# Page06_CPU_IO.net
KiCad netlist of a schematic drawn in Altium Designer
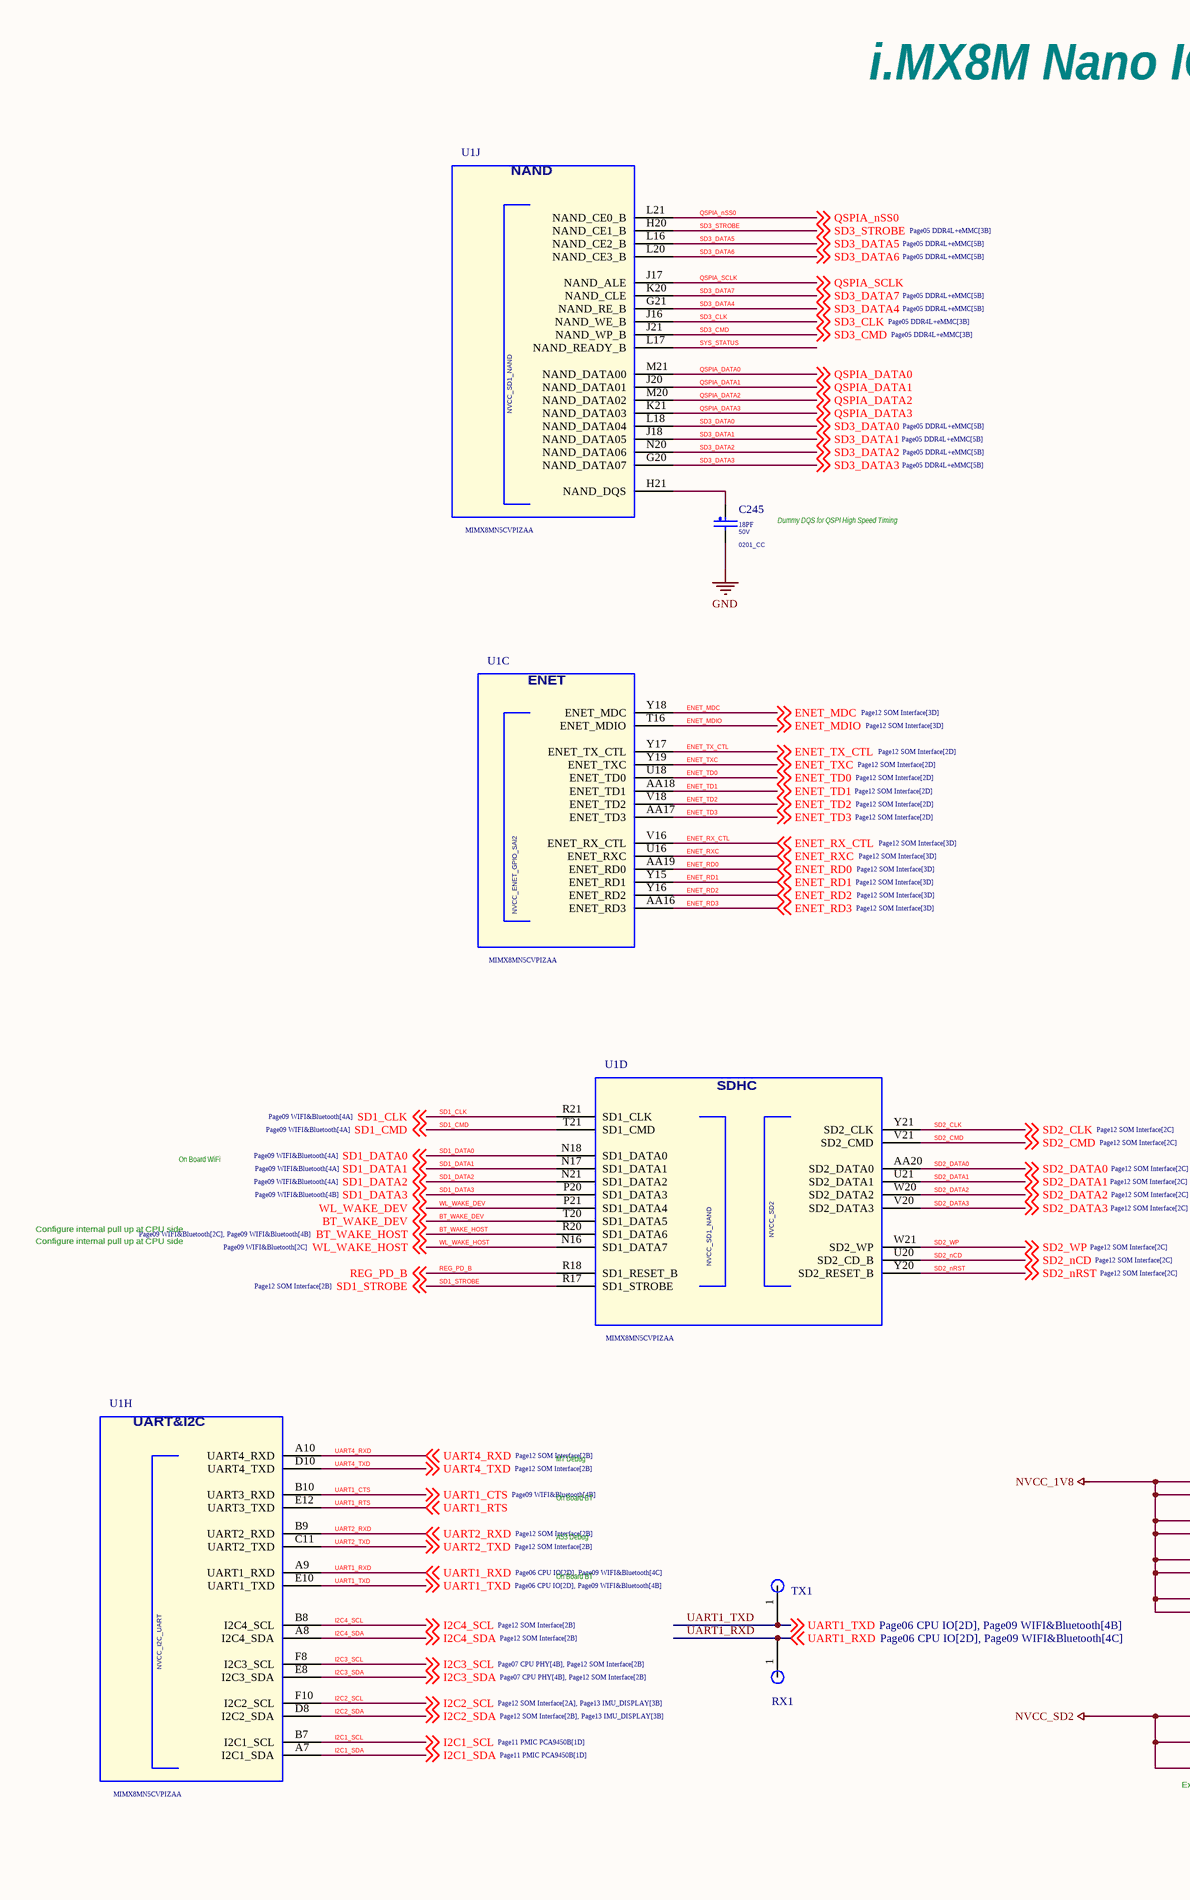
[diagram p0: Page06 CPU IO.SchDoc, left]
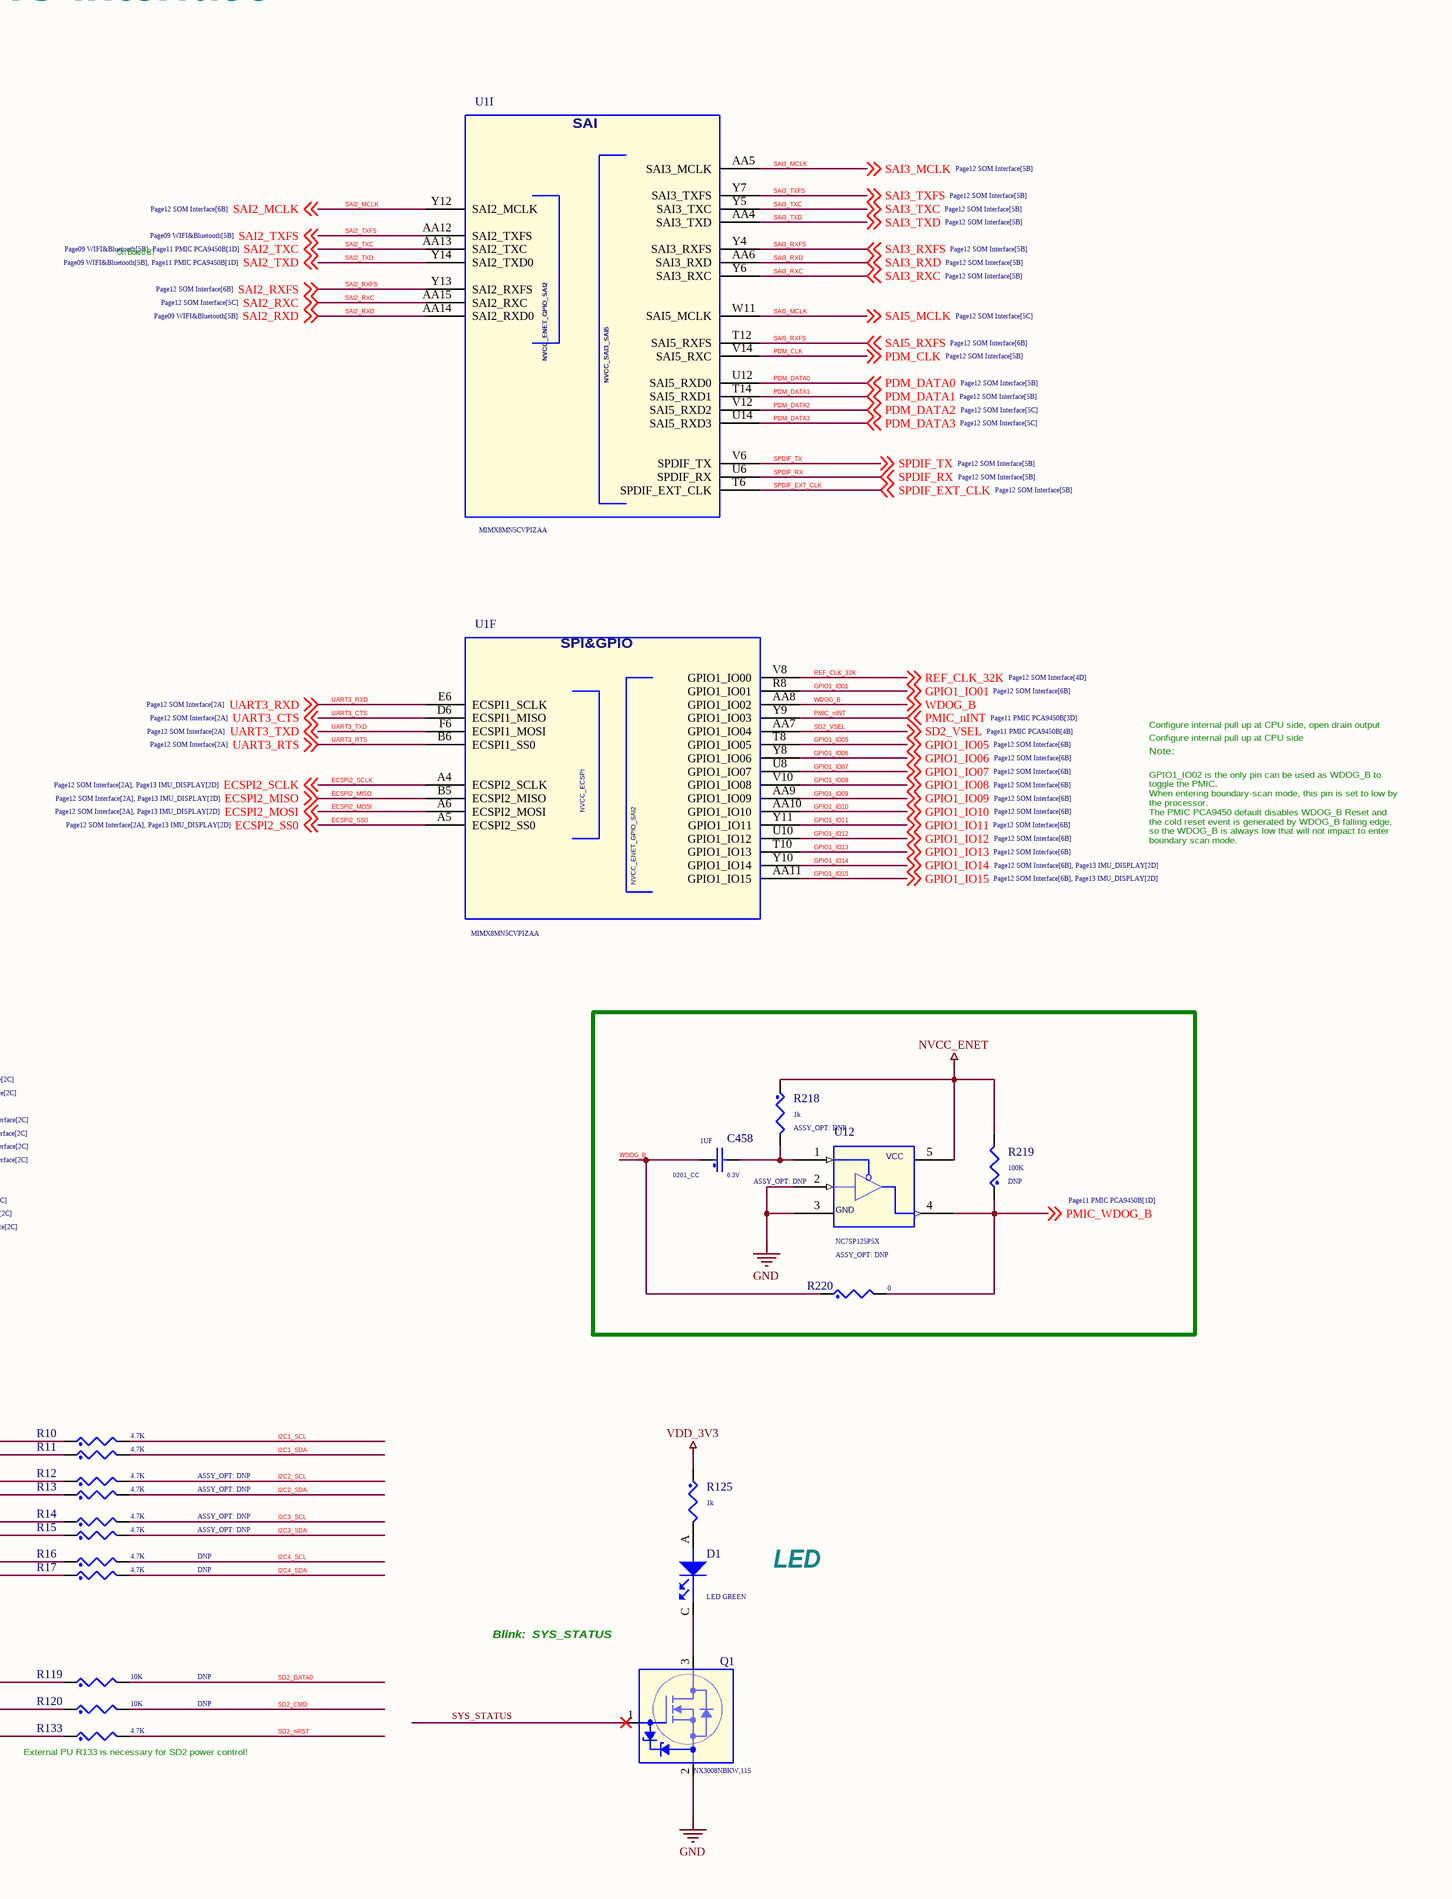
[diagram p1: Page06 CPU IO.SchDoc, right]

(export (version "E")
  (design (tool "Eeschema 10.0.6"))
  (components
    (comp (ref "C245")
      (value "18PF")
      (footprint "0201_CC - C")
      (description "CAP CER 18pF 50V 5% C0G 0201")
      (fields
        (field (name "VOLTAGE") "50V")
        (field (name "TOLERANCE") "5%")
        (field (name "PCB FOOTPRINT") "0201_CC")
      )
      (libsource (lib "*") (part "CAP_NP"))
    )
    (comp (ref "C458")
      (value "1UF")
      (footprint "0201_CC - C")
      (description "CAP CER 1uF 6.3V 20% X5R 0201")
      (fields
        (field (name "ASSY_OPT") "DNP")
        (field (name "PCB FOOTPRINT") "0201_CC")
        (field (name "TOLERANCE") "20%")
        (field (name "VOLTAGE") "6.3V")
      )
      (libsource (lib "*") (part "CAP_NP"))
    )
    (comp (ref "D1")
      (value "LED GREEN")
      (footprint "LED_0603")
      (description "LED GRN SGL 25MA SMT 0603")
      (fields (field (name "VOLTAGE") "2V"))
      (libsource (lib "*") (part "LED"))
    )
    (comp (ref "Q1")
      (value "NX3008NBKW,115")
      (footprint "SOT65P210X110-3N")
      (description "TRAN NMOS SW 30V 350mA AEC-Q101 SC-70")
      (libsource (lib "*") (part "NMOS_NX3008NBK"))
    )
    (comp (ref "R10")
      (value "4.7K")
      (footprint "0201_RES")
      (description "RES MF 4.7K 1/20W 5% AEC-Q200 0201")
      (fields (field (name "TOLERANCE") "5%"))
      (libsource (lib "*") (part "RES"))
    )
    (comp (ref "R11")
      (value "4.7K")
      (footprint "0201_RES")
      (description "RES MF 4.7K 1/20W 5% AEC-Q200 0201")
      (fields (field (name "TOLERANCE") "5%"))
      (libsource (lib "*") (part "RES"))
    )
    (comp (ref "R12")
      (value "4.7K")
      (footprint "0201_RES")
      (description "RES MF 4.7K 1/20W 5% AEC-Q200 0201")
      (fields (field (name "ASSY_OPT") "DNP") (field (name "TOLERANCE") "5%"))
      (libsource (lib "*") (part "RES"))
    )
    (comp (ref "R13")
      (value "4.7K")
      (footprint "0201_RES")
      (description "RES MF 4.7K 1/20W 5% AEC-Q200 0201")
      (fields (field (name "ASSY_OPT") "DNP") (field (name "TOLERANCE") "5%"))
      (libsource (lib "*") (part "RES"))
    )
    (comp (ref "R14")
      (value "4.7K")
      (footprint "0201_RES")
      (description "RES MF 4.7K 1/20W 5% AEC-Q200 0201")
      (fields (field (name "ASSY_OPT") "DNP") (field (name "TOLERANCE") "5%"))
      (libsource (lib "*") (part "RES"))
    )
    (comp (ref "R15")
      (value "4.7K")
      (footprint "0201_RES")
      (description "RES MF 4.7K 1/20W 5% AEC-Q200 0201")
      (fields (field (name "ASSY_OPT") "DNP") (field (name "TOLERANCE") "5%"))
      (libsource (lib "*") (part "RES"))
    )
    (comp (ref "R16")
      (value "4.7K")
      (footprint "0201_RES")
      (description "RES MF 4.7K 1/20W 5% AEC-Q200 0201")
      (fields (field (name "ASSY_OPT") "DNP") (field (name "TOLERANCE") "5%"))
      (libsource (lib "*") (part "RES"))
    )
    (comp (ref "R17")
      (value "4.7K")
      (footprint "0201_RES")
      (description "RES MF 4.7K 1/20W 5% AEC-Q200 0201")
      (fields (field (name "ASSY_OPT") "DNP") (field (name "TOLERANCE") "5%"))
      (libsource (lib "*") (part "RES"))
    )
    (comp (ref "R119")
      (value "10K")
      (footprint "0201_RES")
      (description "RES MF 10K 1/20W 5% 0201")
      (fields (field (name "ASSY_OPT") "DNP") (field (name "TOLERANCE") "5%"))
      (libsource (lib "*") (part "RES"))
    )
    (comp (ref "R120")
      (value "10K")
      (footprint "0201_RES")
      (description "RES MF 10K 1/20W 5% 0201")
      (fields (field (name "ASSY_OPT") "DNP") (field (name "TOLERANCE") "5%"))
      (libsource (lib "*") (part "RES"))
    )
    (comp (ref "R125")
      (value "1k")
      (footprint "0201_RES")
      (description "RES MF 1.0K OHM 1/20W 1% 30V -55+155C 0201")
      (fields (field (name "VOLTAGE") "30") (field (name "TOLERANCE") "1%"))
      (libsource (lib "*") (part "RES"))
    )
    (comp (ref "R133")
      (value "4.7K")
      (footprint "0201_RES")
      (description "RES MF 4.7K 1/20W 5% AEC-Q200 0201")
      (fields (field (name "TOLERANCE") "5%"))
      (libsource (lib "*") (part "RES"))
    )
    (comp (ref "R218")
      (value "1k")
      (footprint "0201_RES")
      (description "RES MF 1.0K OHM 1/20W 1% 30V -55+155C 0201")
      (fields (field (name "ASSY_OPT") "DNP") (field (name "TOLERANCE") "1%") (field (name "VOLTAGE") "30"))
      (libsource (lib "*") (part "RES"))
    )
    (comp (ref "R219")
      (value "100K")
      (footprint "0201_RES")
      (description "RES MF 100K 1/20W 1% 0201")
      (fields (field (name "ASSY_OPT") "DNP") (field (name "TOLERANCE") "1%"))
      (libsource (lib "*") (part "RES"))
    )
    (comp (ref "R220")
      (value "0")
      (footprint "0402_CC_RES")
      (description "RES MF ZERO OHM 1/16W 5% 0402")
      (fields (field (name "TOLERANCE") "5%") (field (name "VOLTAGE") "1/16W"))
      (libsource (lib "*") (part "RES"))
    )
    (comp (ref "RX1")
      (value "Test Pin1")
      (footprint "Test Pin")
      (libsource (lib "Altium starter project NANO") (part "Test Pin1"))
    )
    (comp (ref "TX1")
      (value "Test Pin1")
      (footprint "Test Pin")
      (libsource (lib "Altium starter project NANO") (part "Test Pin1"))
    )
    (comp (ref "U1")
      (value "MIMX8MN5CVPIZAA")
      (footprint "BGA306C50P21X21_1100X1100X101")
      (description "IC CPU QUAD CORTEX A53+M7 1.4GHZ -- BGA306")
      (libsource (lib "*") (part "MIMX8MN"))
    )
    (comp (ref "U12")
      (value "NC7SP125P5X")
      (footprint "FP-MAA05A-IPC_B")
      (description "IC BUF TS 0.9-3.6V")
      (fields (field (name "ASSY_OPT") "DNP"))
      (libsource (lib "*") (part "1G125"))
    )
  )
  (nets
    (net (code "1") (name "/SYS_STATUS") (class "Default")
      (node (ref "Q1") (pin "1") (pinfunction "GATE_1") (pintype "passive"))
      (node (ref "U1") (pin "L17") (pinfunction "NAND_READY_B_L17") (pintype "passive"))
    )
    (net (code "2") (name "BT_WAKE_DEV") (class "Default")
      (node (ref "U1") (pin "T20") (pinfunction "SD1_DATA5_T20") (pintype "passive"))
    )
    (net (code "3") (name "BT_WAKE_HOST") (class "Default")
      (node (ref "U1") (pin "R20") (pinfunction "SD1_DATA6_R20") (pintype "passive"))
    )
    (net (code "4") (name "ECSPI2_MISO") (class "Default")
      (node (ref "U1") (pin "B5") (pinfunction "ECSPI2_MISO_B5") (pintype "passive"))
    )
    (net (code "5") (name "ECSPI2_MOSI") (class "Default")
      (node (ref "U1") (pin "A6") (pinfunction "ECSPI2_MOSI_A6") (pintype "passive"))
    )
    (net (code "6") (name "ECSPI2_SCLK") (class "Default")
      (node (ref "U1") (pin "A4") (pinfunction "ECSPI2_SCLK_A4") (pintype "passive"))
    )
    (net (code "7") (name "ECSPI2_SS0") (class "Default")
      (node (ref "U1") (pin "A5") (pinfunction "ECSPI2_SS0_A5") (pintype "passive"))
    )
    (net (code "8") (name "ENET_MDC") (class "Default")
      (node (ref "U1") (pin "Y18") (pinfunction "ENET_MDC_Y18") (pintype "passive"))
    )
    (net (code "9") (name "ENET_MDIO") (class "Default")
      (node (ref "U1") (pin "T16") (pinfunction "ENET_MDIO_T16") (pintype "passive"))
    )
    (net (code "10") (name "ENET_RD0") (class "Default")
      (node (ref "U1") (pin "AA19") (pinfunction "ENET_RD0_AA19") (pintype "passive"))
    )
    (net (code "11") (name "ENET_RD1") (class "Default")
      (node (ref "U1") (pin "Y15") (pinfunction "ENET_RD1_Y15") (pintype "passive"))
    )
    (net (code "12") (name "ENET_RD2") (class "Default")
      (node (ref "U1") (pin "Y16") (pinfunction "ENET_RD2_Y16") (pintype "passive"))
    )
    (net (code "13") (name "ENET_RD3") (class "Default")
      (node (ref "U1") (pin "AA16") (pinfunction "ENET_RD3_AA16") (pintype "passive"))
    )
    (net (code "14") (name "ENET_RXC") (class "Default")
      (node (ref "U1") (pin "U16") (pinfunction "ENET_RXC_U16") (pintype "passive"))
    )
    (net (code "15") (name "ENET_RX_CTL") (class "Default")
      (node (ref "U1") (pin "V16") (pinfunction "ENET_RX_CTL_V16") (pintype "passive"))
    )
    (net (code "16") (name "ENET_TD0") (class "Default")
      (node (ref "U1") (pin "U18") (pinfunction "ENET_TD0_U18") (pintype "passive"))
    )
    (net (code "17") (name "ENET_TD1") (class "Default")
      (node (ref "U1") (pin "AA18") (pinfunction "ENET_TD1_AA18") (pintype "passive"))
    )
    (net (code "18") (name "ENET_TD2") (class "Default")
      (node (ref "U1") (pin "V18") (pinfunction "ENET_TD2_V18") (pintype "passive"))
    )
    (net (code "19") (name "ENET_TD3") (class "Default")
      (node (ref "U1") (pin "AA17") (pinfunction "ENET_TD3_AA17") (pintype "passive"))
    )
    (net (code "20") (name "ENET_TXC") (class "Default")
      (node (ref "U1") (pin "Y19") (pinfunction "ENET_TXC_Y19") (pintype "passive"))
    )
    (net (code "21") (name "ENET_TX_CTL") (class "Default")
      (node (ref "U1") (pin "Y17") (pinfunction "ENET_TX_CTL_Y17") (pintype "passive"))
    )
    (net (code "22") (name "GND") (class "Default")
      (node (ref "C245") (pin "2") (pinfunction "2_2") (pintype "passive"))
      (node (ref "Q1") (pin "2") (pinfunction "SOURCE_2") (pintype "passive"))
      (node (ref "U12") (pin "2") (pinfunction "A_2") (pintype "input"))
      (node (ref "U12") (pin "3") (pinfunction "GND_3") (pintype "power_in"))
    )
    (net (code "23") (name "GPIO1_IO01") (class "Default")
      (node (ref "U1") (pin "R8") (pinfunction "GPIO1_IO01_R8") (pintype "passive"))
    )
    (net (code "24") (name "GPIO1_IO05") (class "Default")
      (node (ref "U1") (pin "T8") (pinfunction "GPIO1_IO05_T8") (pintype "passive"))
    )
    (net (code "25") (name "GPIO1_IO06") (class "Default")
      (node (ref "U1") (pin "Y8") (pinfunction "GPIO1_IO06_Y8") (pintype "passive"))
    )
    (net (code "26") (name "GPIO1_IO07") (class "Default")
      (node (ref "U1") (pin "U8") (pinfunction "GPIO1_IO07_U8") (pintype "passive"))
    )
    (net (code "27") (name "GPIO1_IO08") (class "Default")
      (node (ref "U1") (pin "V10") (pinfunction "GPIO1_IO08_V10") (pintype "passive"))
    )
    (net (code "28") (name "GPIO1_IO09") (class "Default")
      (node (ref "U1") (pin "AA9") (pinfunction "GPIO1_IO09_AA9") (pintype "passive"))
    )
    (net (code "29") (name "GPIO1_IO10") (class "Default")
      (node (ref "U1") (pin "AA10") (pinfunction "GPIO1_IO10_AA10") (pintype "passive"))
    )
    (net (code "30") (name "GPIO1_IO11") (class "Default")
      (node (ref "U1") (pin "Y11") (pinfunction "GPIO1_IO11_Y11") (pintype "passive"))
    )
    (net (code "31") (name "GPIO1_IO12") (class "Default")
      (node (ref "U1") (pin "U10") (pinfunction "GPIO1_IO12_U10") (pintype "passive"))
    )
    (net (code "32") (name "GPIO1_IO13") (class "Default")
      (node (ref "U1") (pin "T10") (pinfunction "GPIO1_IO13_T10") (pintype "passive"))
    )
    (net (code "33") (name "GPIO1_IO14") (class "Default")
      (node (ref "U1") (pin "Y10") (pinfunction "GPIO1_IO14_Y10") (pintype "passive"))
    )
    (net (code "34") (name "GPIO1_IO15") (class "Default")
      (node (ref "U1") (pin "AA11") (pinfunction "GPIO1_IO15_AA11") (pintype "passive"))
    )
    (net (code "35") (name "I2C1_SCL") (class "Default")
      (node (ref "R10") (pin "2") (pinfunction "2_2") (pintype "passive"))
      (node (ref "U1") (pin "B7") (pinfunction "I2C1_SCL_B7") (pintype "passive"))
    )
    (net (code "36") (name "I2C1_SDA") (class "Default")
      (node (ref "R11") (pin "2") (pinfunction "2_2") (pintype "passive"))
      (node (ref "U1") (pin "A7") (pinfunction "I2C1_SDA_A7") (pintype "passive"))
    )
    (net (code "37") (name "I2C2_SCL") (class "Default")
      (node (ref "R12") (pin "2") (pinfunction "2_2") (pintype "passive"))
      (node (ref "U1") (pin "F10") (pinfunction "I2C2_SCL_F10") (pintype "passive"))
    )
    (net (code "38") (name "I2C2_SDA") (class "Default")
      (node (ref "R13") (pin "2") (pinfunction "2_2") (pintype "passive"))
      (node (ref "U1") (pin "D8") (pinfunction "I2C2_SDA_D8") (pintype "passive"))
    )
    (net (code "39") (name "I2C3_SCL") (class "Default")
      (node (ref "R14") (pin "2") (pinfunction "2_2") (pintype "passive"))
      (node (ref "U1") (pin "F8") (pinfunction "I2C3_SCL_F8") (pintype "passive"))
    )
    (net (code "40") (name "I2C3_SDA") (class "Default")
      (node (ref "R15") (pin "2") (pinfunction "2_2") (pintype "passive"))
      (node (ref "U1") (pin "E8") (pinfunction "I2C3_SDA_E8") (pintype "passive"))
    )
    (net (code "41") (name "I2C4_SCL") (class "Default")
      (node (ref "R16") (pin "2") (pinfunction "2_2") (pintype "passive"))
      (node (ref "U1") (pin "B8") (pinfunction "I2C4_SCL_B8") (pintype "passive"))
    )
    (net (code "42") (name "I2C4_SDA") (class "Default")
      (node (ref "R17") (pin "2") (pinfunction "2_2") (pintype "passive"))
      (node (ref "U1") (pin "A8") (pinfunction "I2C4_SDA_A8") (pintype "passive"))
    )
    (net (code "43") (name "NVCC_1V8") (class "Default")
      (node (ref "R10") (pin "1") (pinfunction "1_1") (pintype "passive"))
      (node (ref "R11") (pin "1") (pinfunction "1_1") (pintype "passive"))
      (node (ref "R12") (pin "1") (pinfunction "1_1") (pintype "passive"))
      (node (ref "R13") (pin "1") (pinfunction "1_1") (pintype "passive"))
      (node (ref "R14") (pin "1") (pinfunction "1_1") (pintype "passive"))
      (node (ref "R15") (pin "1") (pinfunction "1_1") (pintype "passive"))
      (node (ref "R16") (pin "1") (pinfunction "1_1") (pintype "passive"))
      (node (ref "R17") (pin "1") (pinfunction "1_1") (pintype "passive"))
    )
    (net (code "44") (name "NVCC_ENET") (class "Default")
      (node (ref "R218") (pin "1") (pinfunction "1_1") (pintype "passive"))
      (node (ref "R219") (pin "2") (pinfunction "2_2") (pintype "passive"))
      (node (ref "U12") (pin "5") (pinfunction "VCC_5") (pintype "power_in"))
    )
    (net (code "45") (name "NVCC_SD2") (class "Default")
      (node (ref "R119") (pin "1") (pinfunction "1_1") (pintype "passive"))
      (node (ref "R120") (pin "1") (pinfunction "1_1") (pintype "passive"))
      (node (ref "R133") (pin "1") (pinfunction "1_1") (pintype "passive"))
    )
    (net (code "46") (name "Net-(D1-ANODE)") (class "Default")
      (node (ref "D1") (pin "A") (pinfunction "ANODE_A") (pintype "passive"))
      (node (ref "R125") (pin "2") (pinfunction "2_2") (pintype "passive"))
    )
    (net (code "47") (name "Net-(D1-CATHODE)") (class "Default")
      (node (ref "D1") (pin "C") (pinfunction "CATHODE_C") (pintype "passive"))
      (node (ref "Q1") (pin "3") (pinfunction "DRAIN_3") (pintype "passive"))
    )
    (net (code "48") (name "Net-(U1J-NAND_DQS)") (class "Default")
      (node (ref "C245") (pin "1") (pinfunction "1_1") (pintype "passive"))
      (node (ref "U1") (pin "H21") (pinfunction "NAND_DQS_H21") (pintype "passive"))
    )
    (net (code "49") (name "Net-(U12-~{OE})") (class "Default")
      (node (ref "C458") (pin "2") (pinfunction "2_2") (pintype "passive"))
      (node (ref "R218") (pin "2") (pinfunction "2_2") (pintype "passive"))
      (node (ref "U12") (pin "1") (pinfunction "~{OE}_1") (pintype "input"))
    )
    (net (code "50") (name "PDM_CLK") (class "Default")
      (node (ref "U1") (pin "V14") (pinfunction "SAI5_RXC_V14") (pintype "passive"))
    )
    (net (code "51") (name "PDM_DATA0") (class "Default")
      (node (ref "U1") (pin "U12") (pinfunction "SAI5_RXD0_U12") (pintype "passive"))
    )
    (net (code "52") (name "PDM_DATA1") (class "Default")
      (node (ref "U1") (pin "T14") (pinfunction "SAI5_RXD1_T14") (pintype "passive"))
    )
    (net (code "53") (name "PDM_DATA2") (class "Default")
      (node (ref "U1") (pin "V12") (pinfunction "SAI5_RXD2_V12") (pintype "passive"))
    )
    (net (code "54") (name "PDM_DATA3") (class "Default")
      (node (ref "U1") (pin "U14") (pinfunction "SAI5_RXD3_U14") (pintype "passive"))
    )
    (net (code "55") (name "PMIC_WDOG_B") (class "Default")
      (node (ref "R219") (pin "1") (pinfunction "1_1") (pintype "passive"))
      (node (ref "R220") (pin "2") (pinfunction "2_2") (pintype "passive"))
      (node (ref "U12") (pin "4") (pinfunction "Y_4") (pintype "output"))
    )
    (net (code "56") (name "PMIC_nINT") (class "Default")
      (node (ref "U1") (pin "Y9") (pinfunction "GPIO1_IO03_Y9") (pintype "passive"))
    )
    (net (code "57") (name "QSPIA_DATA0") (class "Default")
      (node (ref "U1") (pin "M21") (pinfunction "NAND_DATA00_M21") (pintype "passive"))
    )
    (net (code "58") (name "QSPIA_DATA1") (class "Default")
      (node (ref "U1") (pin "J20") (pinfunction "NAND_DATA01_J20") (pintype "passive"))
    )
    (net (code "59") (name "QSPIA_DATA2") (class "Default")
      (node (ref "U1") (pin "M20") (pinfunction "NAND_DATA02_M20") (pintype "passive"))
    )
    (net (code "60") (name "QSPIA_DATA3") (class "Default")
      (node (ref "U1") (pin "K21") (pinfunction "NAND_DATA03_K21") (pintype "passive"))
    )
    (net (code "61") (name "QSPIA_SCLK") (class "Default")
      (node (ref "U1") (pin "J17") (pinfunction "NAND_ALE_J17") (pintype "passive"))
    )
    (net (code "62") (name "QSPIA_nSS0") (class "Default")
      (node (ref "U1") (pin "L21") (pinfunction "NAND_CE0_B_L21") (pintype "passive"))
    )
    (net (code "63") (name "REF_CLK_32K") (class "Default")
      (node (ref "U1") (pin "V8") (pinfunction "GPIO1_IO00_V8") (pintype "passive"))
    )
    (net (code "64") (name "REG_PD_B") (class "Default")
      (node (ref "U1") (pin "R18") (pinfunction "SD1_RESET_B_R18") (pintype "passive"))
    )
    (net (code "65") (name "SAI2_MCLK") (class "Default")
      (node (ref "U1") (pin "Y12") (pinfunction "SAI2_MCLK_Y12") (pintype "passive"))
    )
    (net (code "66") (name "SAI2_RXC") (class "Default")
      (node (ref "U1") (pin "AA15") (pinfunction "SAI2_RXC_AA15") (pintype "passive"))
    )
    (net (code "67") (name "SAI2_RXD") (class "Default")
      (node (ref "U1") (pin "AA14") (pinfunction "SAI2_RXD0_AA14") (pintype "passive"))
    )
    (net (code "68") (name "SAI2_RXFS") (class "Default")
      (node (ref "U1") (pin "Y13") (pinfunction "SAI2_RXFS_Y13") (pintype "passive"))
    )
    (net (code "69") (name "SAI2_TXC") (class "Default")
      (node (ref "U1") (pin "AA13") (pinfunction "SAI2_TXC_AA13") (pintype "passive"))
    )
    (net (code "70") (name "SAI2_TXD") (class "Default")
      (node (ref "U1") (pin "Y14") (pinfunction "SAI2_TXD0_Y14") (pintype "passive"))
    )
    (net (code "71") (name "SAI2_TXFS") (class "Default")
      (node (ref "U1") (pin "AA12") (pinfunction "SAI2_TXFS_AA12") (pintype "passive"))
    )
    (net (code "72") (name "SAI3_MCLK") (class "Default")
      (node (ref "U1") (pin "AA5") (pinfunction "SAI3_MCLK_AA5") (pintype "passive"))
    )
    (net (code "73") (name "SAI3_RXC") (class "Default")
      (node (ref "U1") (pin "Y6") (pinfunction "SAI3_RXC_Y6") (pintype "passive"))
    )
    (net (code "74") (name "SAI3_RXD") (class "Default")
      (node (ref "U1") (pin "AA6") (pinfunction "SAI3_RXD_AA6") (pintype "passive"))
    )
    (net (code "75") (name "SAI3_RXFS") (class "Default")
      (node (ref "U1") (pin "Y4") (pinfunction "SAI3_RXFS_Y4") (pintype "passive"))
    )
    (net (code "76") (name "SAI3_TXC") (class "Default")
      (node (ref "U1") (pin "Y5") (pinfunction "SAI3_TXC_Y5") (pintype "passive"))
    )
    (net (code "77") (name "SAI3_TXD") (class "Default")
      (node (ref "U1") (pin "AA4") (pinfunction "SAI3_TXD_AA4") (pintype "passive"))
    )
    (net (code "78") (name "SAI3_TXFS") (class "Default")
      (node (ref "U1") (pin "Y7") (pinfunction "SAI3_TXFS_Y7") (pintype "passive"))
    )
    (net (code "79") (name "SAI5_MCLK") (class "Default")
      (node (ref "U1") (pin "W11") (pinfunction "SAI5_MCLK_W11") (pintype "passive"))
    )
    (net (code "80") (name "SAI5_RXFS") (class "Default")
      (node (ref "U1") (pin "T12") (pinfunction "SAI5_RXFS_T12") (pintype "passive"))
    )
    (net (code "81") (name "SD1_CLK") (class "Default")
      (node (ref "U1") (pin "R21") (pinfunction "SD1_CLK_R21") (pintype "passive"))
    )
    (net (code "82") (name "SD1_CMD") (class "Default")
      (node (ref "U1") (pin "T21") (pinfunction "SD1_CMD_T21") (pintype "passive"))
    )
    (net (code "83") (name "SD1_DATA0") (class "Default")
      (node (ref "U1") (pin "N18") (pinfunction "SD1_DATA0_N18") (pintype "passive"))
    )
    (net (code "84") (name "SD1_DATA1") (class "Default")
      (node (ref "U1") (pin "N17") (pinfunction "SD1_DATA1_N17") (pintype "passive"))
    )
    (net (code "85") (name "SD1_DATA2") (class "Default")
      (node (ref "U1") (pin "N21") (pinfunction "SD1_DATA2_N21") (pintype "passive"))
    )
    (net (code "86") (name "SD1_DATA3") (class "Default")
      (node (ref "U1") (pin "P20") (pinfunction "SD1_DATA3_P20") (pintype "passive"))
    )
    (net (code "87") (name "SD1_STROBE") (class "Default")
      (node (ref "U1") (pin "R17") (pinfunction "SD1_STROBE_R17") (pintype "passive"))
    )
    (net (code "88") (name "SD2_CLK") (class "Default")
      (node (ref "U1") (pin "Y21") (pinfunction "SD2_CLK_Y21") (pintype "passive"))
    )
    (net (code "89") (name "SD2_CMD") (class "Default")
      (node (ref "R120") (pin "2") (pinfunction "2_2") (pintype "passive"))
      (node (ref "U1") (pin "V21") (pinfunction "SD2_CMD_V21") (pintype "passive"))
    )
    (net (code "90") (name "SD2_DATA0") (class "Default")
      (node (ref "R119") (pin "2") (pinfunction "2_2") (pintype "passive"))
      (node (ref "U1") (pin "AA20") (pinfunction "SD2_DATA0_AA20") (pintype "passive"))
    )
    (net (code "91") (name "SD2_DATA1") (class "Default")
      (node (ref "U1") (pin "U21") (pinfunction "SD2_DATA1_U21") (pintype "passive"))
    )
    (net (code "92") (name "SD2_DATA2") (class "Default")
      (node (ref "U1") (pin "W20") (pinfunction "SD2_DATA2_W20") (pintype "passive"))
    )
    (net (code "93") (name "SD2_DATA3") (class "Default")
      (node (ref "U1") (pin "V20") (pinfunction "SD2_DATA3_V20") (pintype "passive"))
    )
    (net (code "94") (name "SD2_VSEL") (class "Default")
      (node (ref "U1") (pin "AA7") (pinfunction "GPIO1_IO04_AA7") (pintype "passive"))
    )
    (net (code "95") (name "SD2_WP") (class "Default")
      (node (ref "U1") (pin "W21") (pinfunction "SD2_WP_W21") (pintype "passive"))
    )
    (net (code "96") (name "SD2_nCD") (class "Default")
      (node (ref "U1") (pin "U20") (pinfunction "SD2_CD_B_U20") (pintype "passive"))
    )
    (net (code "97") (name "SD2_nRST") (class "Default")
      (node (ref "R133") (pin "2") (pinfunction "2_2") (pintype "passive"))
      (node (ref "U1") (pin "Y20") (pinfunction "SD2_RESET_B_Y20") (pintype "passive"))
    )
    (net (code "98") (name "SD3_CLK") (class "Default")
      (node (ref "U1") (pin "J16") (pinfunction "NAND_WE_B_J16") (pintype "passive"))
    )
    (net (code "99") (name "SD3_CMD") (class "Default")
      (node (ref "U1") (pin "J21") (pinfunction "NAND_WP_B_J21") (pintype "passive"))
    )
    (net (code "100") (name "SD3_DATA0") (class "Default")
      (node (ref "U1") (pin "L18") (pinfunction "NAND_DATA04_L18") (pintype "passive"))
    )
    (net (code "101") (name "SD3_DATA1") (class "Default")
      (node (ref "U1") (pin "J18") (pinfunction "NAND_DATA05_J18") (pintype "passive"))
    )
    (net (code "102") (name "SD3_DATA2") (class "Default")
      (node (ref "U1") (pin "N20") (pinfunction "NAND_DATA06_N20") (pintype "passive"))
    )
    (net (code "103") (name "SD3_DATA3") (class "Default")
      (node (ref "U1") (pin "G20") (pinfunction "NAND_DATA07_G20") (pintype "passive"))
    )
    (net (code "104") (name "SD3_DATA4") (class "Default")
      (node (ref "U1") (pin "G21") (pinfunction "NAND_RE_B_G21") (pintype "passive"))
    )
    (net (code "105") (name "SD3_DATA5") (class "Default")
      (node (ref "U1") (pin "L16") (pinfunction "NAND_CE2_B_L16") (pintype "passive"))
    )
    (net (code "106") (name "SD3_DATA6") (class "Default")
      (node (ref "U1") (pin "L20") (pinfunction "NAND_CE3_B_L20") (pintype "passive"))
    )
    (net (code "107") (name "SD3_DATA7") (class "Default")
      (node (ref "U1") (pin "K20") (pinfunction "NAND_CLE_K20") (pintype "passive"))
    )
    (net (code "108") (name "SD3_STROBE") (class "Default")
      (node (ref "U1") (pin "H20") (pinfunction "NAND_CE1_B_H20") (pintype "passive"))
    )
    (net (code "109") (name "SPDIF_EXT_CLK") (class "Default")
      (node (ref "U1") (pin "T6") (pinfunction "SPDIF_EXT_CLK_T6") (pintype "passive"))
    )
    (net (code "110") (name "SPDIF_RX") (class "Default")
      (node (ref "U1") (pin "U6") (pinfunction "SPDIF_RX_U6") (pintype "passive"))
    )
    (net (code "111") (name "SPDIF_TX") (class "Default")
      (node (ref "U1") (pin "V6") (pinfunction "SPDIF_TX_V6") (pintype "passive"))
    )
    (net (code "112") (name "UART1_CTS") (class "Default")
      (node (ref "U1") (pin "B10") (pinfunction "UART3_RXD_B10") (pintype "passive"))
    )
    (net (code "113") (name "UART1_RTS") (class "Default")
      (node (ref "U1") (pin "E12") (pinfunction "UART3_TXD_E12") (pintype "passive"))
    )
    (net (code "114") (name "UART1_RXD") (class "Default")
      (node (ref "RX1") (pin "1") (pinfunction "1_1") (pintype "passive"))
      (node (ref "U1") (pin "A9") (pinfunction "UART1_RXD_A9") (pintype "passive"))
    )
    (net (code "115") (name "UART1_TXD") (class "Default")
      (node (ref "TX1") (pin "1") (pinfunction "1_1") (pintype "passive"))
      (node (ref "U1") (pin "E10") (pinfunction "UART1_TXD_E10") (pintype "passive"))
    )
    (net (code "116") (name "UART2_RXD") (class "Default")
      (node (ref "U1") (pin "B9") (pinfunction "UART2_RXD_B9") (pintype "passive"))
    )
    (net (code "117") (name "UART2_TXD") (class "Default")
      (node (ref "U1") (pin "C11") (pinfunction "UART2_TXD_C11") (pintype "passive"))
    )
    (net (code "118") (name "UART3_CTS") (class "Default")
      (node (ref "U1") (pin "D6") (pinfunction "ECSPI1_MISO_D6") (pintype "passive"))
    )
    (net (code "119") (name "UART3_RTS") (class "Default")
      (node (ref "U1") (pin "B6") (pinfunction "ECSPI1_SS0_B6") (pintype "passive"))
    )
    (net (code "120") (name "UART3_RXD") (class "Default")
      (node (ref "U1") (pin "E6") (pinfunction "ECSPI1_SCLK_E6") (pintype "passive"))
    )
    (net (code "121") (name "UART3_TXD") (class "Default")
      (node (ref "U1") (pin "F6") (pinfunction "ECSPI1_MOSI_F6") (pintype "passive"))
    )
    (net (code "122") (name "UART4_RXD") (class "Default")
      (node (ref "U1") (pin "A10") (pinfunction "UART4_RXD_A10") (pintype "passive"))
    )
    (net (code "123") (name "UART4_TXD") (class "Default")
      (node (ref "U1") (pin "D10") (pinfunction "UART4_TXD_D10") (pintype "passive"))
    )
    (net (code "124") (name "VDD_3V3") (class "Default")
      (node (ref "R125") (pin "1") (pinfunction "1_1") (pintype "passive"))
    )
    (net (code "125") (name "WDOG_B") (class "Default")
      (node (ref "C458") (pin "1") (pinfunction "1_1") (pintype "passive"))
      (node (ref "R220") (pin "1") (pinfunction "1_1") (pintype "passive"))
      (node (ref "U1") (pin "AA8") (pinfunction "GPIO1_IO02_AA8") (pintype "passive"))
    )
    (net (code "126") (name "WL_WAKE_DEV") (class "Default")
      (node (ref "U1") (pin "P21") (pinfunction "SD1_DATA4_P21") (pintype "passive"))
    )
    (net (code "127") (name "WL_WAKE_HOST") (class "Default")
      (node (ref "U1") (pin "N16") (pinfunction "SD1_DATA7_N16") (pintype "passive"))
    )
  )
)
